# KeyInput_MG.net
KiCad netlist of a schematic drawn in Altium Designer
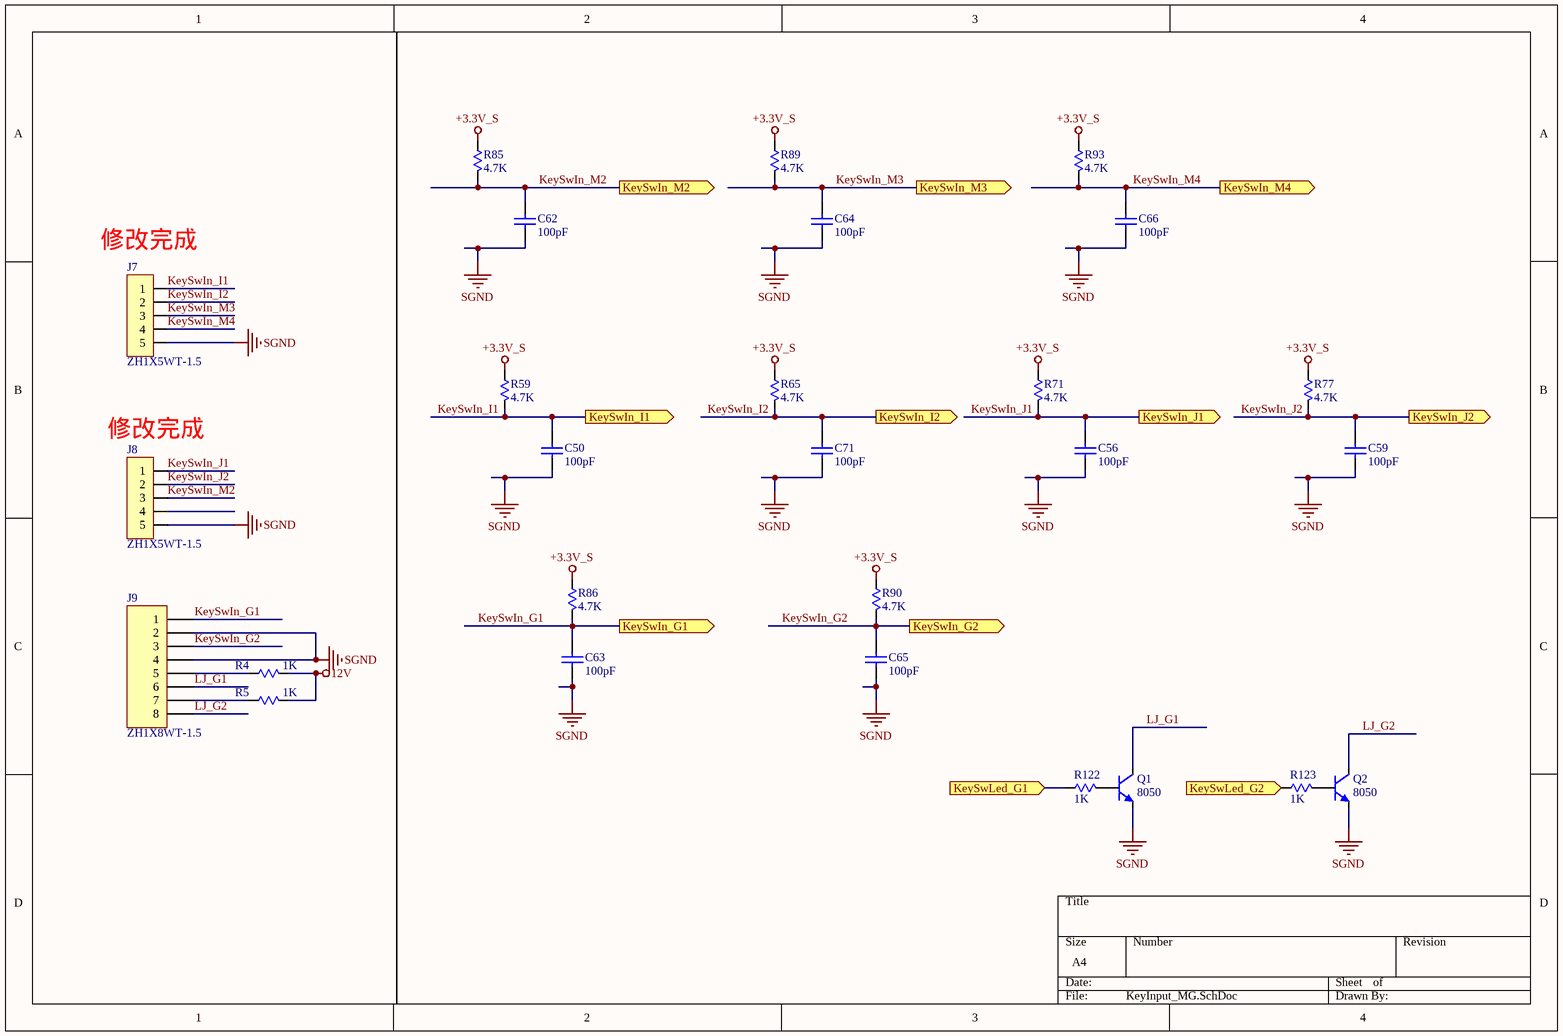
[diagram p0: KeyInput_MG.SchDoc]

(export (version "E")
  (design (tool "Eeschema 10.0.6"))
  (components
    (comp (ref "C50")
      (value "100pF")
      (footprint "C0805")
      (description "Capacitor")
      (fields (field (name "PUBLISHER") "Altium Limited"))
      (libsource (lib "Miscellaneous Devices") (part "Cap"))
    )
    (comp (ref "C56")
      (value "100pF")
      (footprint "C0805")
      (description "Capacitor")
      (fields (field (name "PUBLISHER") "Altium Limited"))
      (libsource (lib "Miscellaneous Devices") (part "Cap"))
    )
    (comp (ref "C59")
      (value "100pF")
      (footprint "C0805")
      (description "Capacitor")
      (fields (field (name "PUBLISHER") "Altium Limited"))
      (libsource (lib "Miscellaneous Devices") (part "Cap"))
    )
    (comp (ref "C62")
      (value "100pF")
      (footprint "C0805")
      (description "Capacitor")
      (fields (field (name "PUBLISHER") "Altium Limited"))
      (libsource (lib "Miscellaneous Devices") (part "Cap"))
    )
    (comp (ref "C63")
      (value "100pF")
      (footprint "C0805")
      (description "Capacitor")
      (fields (field (name "PUBLISHER") "Altium Limited"))
      (libsource (lib "Miscellaneous Devices") (part "Cap"))
    )
    (comp (ref "C64")
      (value "100pF")
      (footprint "C0805")
      (description "Capacitor")
      (fields (field (name "PUBLISHER") "Altium Limited"))
      (libsource (lib "Miscellaneous Devices") (part "Cap"))
    )
    (comp (ref "C65")
      (value "100pF")
      (footprint "C0805")
      (description "Capacitor")
      (fields (field (name "PUBLISHER") "Altium Limited"))
      (libsource (lib "Miscellaneous Devices") (part "Cap"))
    )
    (comp (ref "C66")
      (value "100pF")
      (footprint "C0805")
      (description "Capacitor")
      (fields (field (name "PUBLISHER") "Altium Limited"))
      (libsource (lib "Miscellaneous Devices") (part "Cap"))
    )
    (comp (ref "C71")
      (value "100pF")
      (footprint "C0805")
      (description "Capacitor")
      (fields (field (name "PUBLISHER") "Altium Limited"))
      (libsource (lib "Miscellaneous Devices") (part "Cap"))
    )
    (comp (ref "J7")
      (value "ZH1X5WT-1.5")
      (footprint "ZH1X5WT-1.5")
      (libsource (lib "Connector Class") (part "HEADER1X5"))
    )
    (comp (ref "J8")
      (value "ZH1X5WT-1.5")
      (footprint "ZH1X5WT-1.5")
      (libsource (lib "Connector Class") (part "HEADER1X5"))
    )
    (comp (ref "J9")
      (value "ZH1X8WT-1.5")
      (footprint "ZH1X8WT-1.5")
      (description "Header, 8-Pin")
      (fields (field (name "PUBLISHER") "Altium Limited"))
      (libsource (lib "Miscellaneous Connectors") (part "Header 8"))
    )
    (comp (ref "Q1")
      (value "8050")
      (footprint "SOT-23")
      (description "NPN General Purpose Amplifier")
      (fields (field (name "PUBLISHER") "Altium Limited"))
      (libsource (lib "Bdmc4810") (part "NPN"))
    )
    (comp (ref "Q2")
      (value "8050")
      (footprint "SOT-23")
      (description "NPN General Purpose Amplifier")
      (fields (field (name "PUBLISHER") "Altium Limited"))
      (libsource (lib "Bdmc4810") (part "NPN"))
    )
    (comp (ref "R4")
      (value "1K")
      (footprint "R0805")
      (description "Resistor")
      (fields (field (name "PUBLISHER") "Altium Limited"))
      (libsource (lib "Passive Components Class") (part "RES"))
    )
    (comp (ref "R5")
      (value "1K")
      (footprint "R0805")
      (description "Resistor")
      (fields (field (name "PUBLISHER") "Altium Limited"))
      (libsource (lib "Passive Components Class") (part "RES"))
    )
    (comp (ref "R59")
      (value "4.7K")
      (footprint "R0805")
      (description "Resistor")
      (fields (field (name "PUBLISHER") "Altium Limited"))
      (libsource (lib "Passive Components Class") (part "RES"))
    )
    (comp (ref "R65")
      (value "4.7K")
      (footprint "R0805")
      (description "Resistor")
      (fields (field (name "PUBLISHER") "Altium Limited"))
      (libsource (lib "Passive Components Class") (part "RES"))
    )
    (comp (ref "R71")
      (value "4.7K")
      (footprint "R0805")
      (description "Resistor")
      (fields (field (name "PUBLISHER") "Altium Limited"))
      (libsource (lib "Passive Components Class") (part "RES"))
    )
    (comp (ref "R77")
      (value "4.7K")
      (footprint "R0805")
      (description "Resistor")
      (fields (field (name "PUBLISHER") "Altium Limited"))
      (libsource (lib "Passive Components Class") (part "RES"))
    )
    (comp (ref "R85")
      (value "4.7K")
      (footprint "R0805")
      (description "Resistor")
      (fields (field (name "PUBLISHER") "Altium Limited"))
      (libsource (lib "Passive Components Class") (part "RES"))
    )
    (comp (ref "R86")
      (value "4.7K")
      (footprint "R0805")
      (description "Resistor")
      (fields (field (name "PUBLISHER") "Altium Limited"))
      (libsource (lib "Passive Components Class") (part "RES"))
    )
    (comp (ref "R89")
      (value "4.7K")
      (footprint "R0805")
      (description "Resistor")
      (fields (field (name "PUBLISHER") "Altium Limited"))
      (libsource (lib "Passive Components Class") (part "RES"))
    )
    (comp (ref "R90")
      (value "4.7K")
      (footprint "R0805")
      (description "Resistor")
      (fields (field (name "PUBLISHER") "Altium Limited"))
      (libsource (lib "Passive Components Class") (part "RES"))
    )
    (comp (ref "R93")
      (value "4.7K")
      (footprint "R0805")
      (description "Resistor")
      (fields (field (name "PUBLISHER") "Altium Limited"))
      (libsource (lib "Passive Components Class") (part "RES"))
    )
    (comp (ref "R122")
      (value "1K")
      (footprint "R0805")
      (description "Resistor")
      (fields (field (name "PUBLISHER") "Altium Limited"))
      (libsource (lib "Passive Components Class") (part "RES"))
    )
    (comp (ref "R123")
      (value "1K")
      (footprint "R0805")
      (description "Resistor")
      (fields (field (name "PUBLISHER") "Altium Limited"))
      (libsource (lib "Passive Components Class") (part "RES"))
    )
  )
  (nets
    (net (code "1") (name "+3.3V_S") (class "Default")
      (node (ref "R59") (pin "2") (pinfunction "2_2") (pintype "passive"))
      (node (ref "R65") (pin "2") (pinfunction "2_2") (pintype "passive"))
      (node (ref "R71") (pin "2") (pinfunction "2_2") (pintype "passive"))
      (node (ref "R77") (pin "2") (pinfunction "2_2") (pintype "passive"))
      (node (ref "R85") (pin "2") (pinfunction "2_2") (pintype "passive"))
      (node (ref "R86") (pin "2") (pinfunction "2_2") (pintype "passive"))
      (node (ref "R89") (pin "2") (pinfunction "2_2") (pintype "passive"))
      (node (ref "R90") (pin "2") (pinfunction "2_2") (pintype "passive"))
      (node (ref "R93") (pin "2") (pinfunction "2_2") (pintype "passive"))
    )
    (net (code "2") (name "/KeySwIn_G1") (class "Default")
      (node (ref "C63") (pin "1") (pinfunction "1_1") (pintype "passive"))
      (node (ref "J9") (pin "1") (pinfunction "1_1") (pintype "passive"))
      (node (ref "R86") (pin "1") (pinfunction "1_1") (pintype "passive"))
    )
    (net (code "3") (name "/KeySwIn_G2") (class "Default")
      (node (ref "C65") (pin "1") (pinfunction "1_1") (pintype "passive"))
      (node (ref "J9") (pin "3") (pinfunction "3_3") (pintype "passive"))
      (node (ref "R90") (pin "1") (pinfunction "1_1") (pintype "passive"))
    )
    (net (code "4") (name "/KeySwIn_I1") (class "Default")
      (node (ref "C50") (pin "1") (pinfunction "1_1") (pintype "passive"))
      (node (ref "J7") (pin "1") (pinfunction "1_1") (pintype "passive"))
      (node (ref "R59") (pin "1") (pinfunction "1_1") (pintype "passive"))
    )
    (net (code "5") (name "/KeySwIn_I2") (class "Default")
      (node (ref "C71") (pin "1") (pinfunction "1_1") (pintype "passive"))
      (node (ref "J7") (pin "2") (pinfunction "2_2") (pintype "passive"))
      (node (ref "R65") (pin "1") (pinfunction "1_1") (pintype "passive"))
    )
    (net (code "6") (name "/KeySwIn_J1") (class "Default")
      (node (ref "C56") (pin "1") (pinfunction "1_1") (pintype "passive"))
      (node (ref "J8") (pin "1") (pinfunction "1_1") (pintype "passive"))
      (node (ref "R71") (pin "1") (pinfunction "1_1") (pintype "passive"))
    )
    (net (code "7") (name "/KeySwIn_J2") (class "Default")
      (node (ref "C59") (pin "1") (pinfunction "1_1") (pintype "passive"))
      (node (ref "J8") (pin "2") (pinfunction "2_2") (pintype "passive"))
      (node (ref "R77") (pin "1") (pinfunction "1_1") (pintype "passive"))
    )
    (net (code "8") (name "/KeySwIn_M2") (class "Default")
      (node (ref "C62") (pin "1") (pinfunction "1_1") (pintype "passive"))
      (node (ref "J8") (pin "3") (pinfunction "3_3") (pintype "passive"))
      (node (ref "R85") (pin "1") (pinfunction "1_1") (pintype "passive"))
    )
    (net (code "9") (name "/KeySwIn_M3") (class "Default")
      (node (ref "C64") (pin "1") (pinfunction "1_1") (pintype "passive"))
      (node (ref "J7") (pin "3") (pinfunction "3_3") (pintype "passive"))
      (node (ref "R89") (pin "1") (pinfunction "1_1") (pintype "passive"))
    )
    (net (code "10") (name "/KeySwIn_M4") (class "Default")
      (node (ref "C66") (pin "1") (pinfunction "1_1") (pintype "passive"))
      (node (ref "J7") (pin "4") (pinfunction "4_4") (pintype "passive"))
      (node (ref "R93") (pin "1") (pinfunction "1_1") (pintype "passive"))
    )
    (net (code "11") (name "/KeySwLed_G1") (class "Default")
      (node (ref "R122") (pin "2") (pinfunction "2_2") (pintype "passive"))
    )
    (net (code "12") (name "/KeySwLed_G2") (class "Default")
      (node (ref "R123") (pin "2") (pinfunction "2_2") (pintype "passive"))
    )
    (net (code "13") (name "/LJ_G1") (class "Default")
      (node (ref "J9") (pin "6") (pinfunction "6_6") (pintype "passive"))
      (node (ref "Q1") (pin "3") (pinfunction "C_3") (pintype "passive"))
    )
    (net (code "14") (name "/LJ_G2") (class "Default")
      (node (ref "J9") (pin "8") (pinfunction "8_8") (pintype "passive"))
      (node (ref "Q2") (pin "3") (pinfunction "C_3") (pintype "passive"))
    )
    (net (code "15") (name "12V") (class "Default")
      (node (ref "R4") (pin "1") (pinfunction "1_1") (pintype "passive"))
      (node (ref "R5") (pin "1") (pinfunction "1_1") (pintype "passive"))
    )
    (net (code "16") (name "Net-(J9-Pad5)") (class "Default")
      (node (ref "J9") (pin "5") (pinfunction "5_5") (pintype "passive"))
      (node (ref "R4") (pin "2") (pinfunction "2_2") (pintype "passive"))
    )
    (net (code "17") (name "Net-(J9-Pad7)") (class "Default")
      (node (ref "J9") (pin "7") (pinfunction "7_7") (pintype "passive"))
      (node (ref "R5") (pin "2") (pinfunction "2_2") (pintype "passive"))
    )
    (net (code "18") (name "Net-(Q1-B)") (class "Default")
      (node (ref "Q1") (pin "1") (pinfunction "B_1") (pintype "passive"))
      (node (ref "R122") (pin "1") (pinfunction "1_1") (pintype "passive"))
    )
    (net (code "19") (name "Net-(Q2-B)") (class "Default")
      (node (ref "Q2") (pin "1") (pinfunction "B_1") (pintype "passive"))
      (node (ref "R123") (pin "1") (pinfunction "1_1") (pintype "passive"))
    )
    (net (code "20") (name "SGND") (class "Default")
      (node (ref "C50") (pin "2") (pinfunction "2_2") (pintype "passive"))
      (node (ref "C56") (pin "2") (pinfunction "2_2") (pintype "passive"))
      (node (ref "C59") (pin "2") (pinfunction "2_2") (pintype "passive"))
      (node (ref "C62") (pin "2") (pinfunction "2_2") (pintype "passive"))
      (node (ref "C63") (pin "2") (pinfunction "2_2") (pintype "passive"))
      (node (ref "C64") (pin "2") (pinfunction "2_2") (pintype "passive"))
      (node (ref "C65") (pin "2") (pinfunction "2_2") (pintype "passive"))
      (node (ref "C66") (pin "2") (pinfunction "2_2") (pintype "passive"))
      (node (ref "C71") (pin "2") (pinfunction "2_2") (pintype "passive"))
      (node (ref "J7") (pin "5") (pinfunction "5_5") (pintype "passive"))
      (node (ref "J8") (pin "5") (pinfunction "5_5") (pintype "passive"))
      (node (ref "J9") (pin "2") (pinfunction "2_2") (pintype "passive"))
      (node (ref "J9") (pin "4") (pinfunction "4_4") (pintype "passive"))
      (node (ref "Q1") (pin "2") (pinfunction "E_2") (pintype "passive"))
      (node (ref "Q2") (pin "2") (pinfunction "E_2") (pintype "passive"))
    )
    (net (code "21") (name "unconnected-(J8-Pad4)") (class "Default")
      (node (ref "J8") (pin "4") (pinfunction "4_4") (pintype "passive"))
    )
  )
)
